# keyboard.net
KiCad netlist of a schematic drawn in Altium Designer
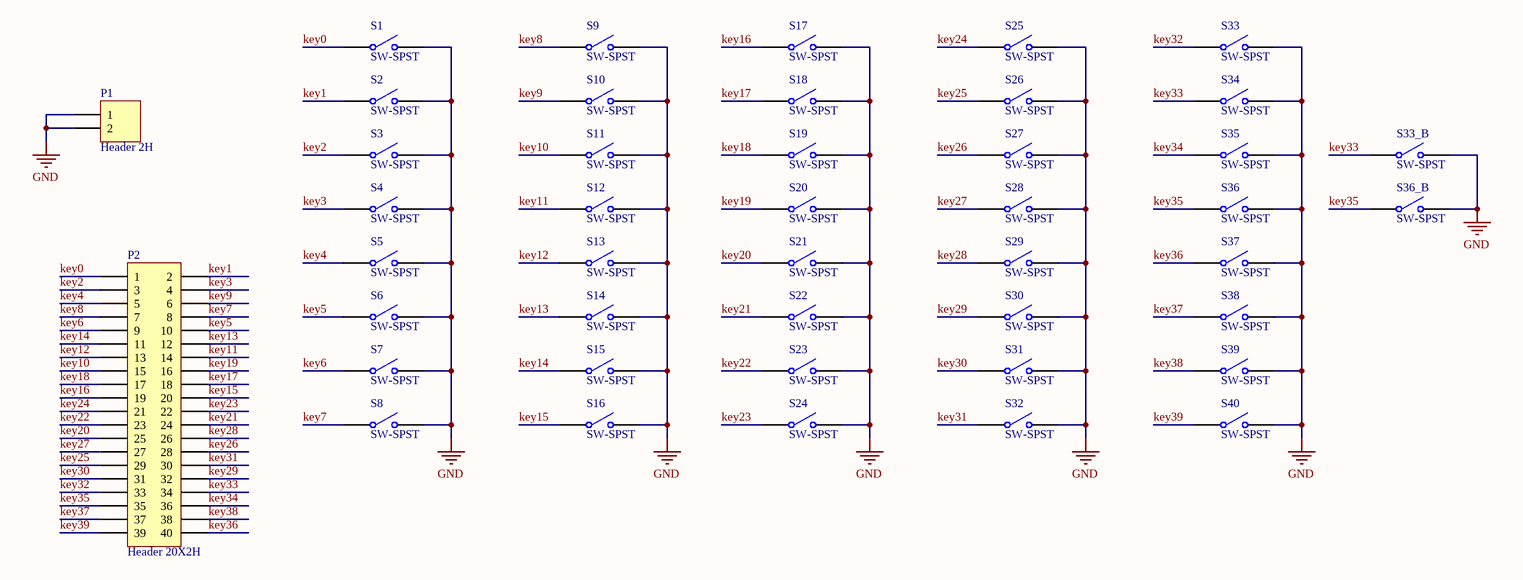
[diagram p0: keyboard.SchDoc]

(export (version "E")
  (design (tool "Eeschema 10.0.6"))
  (components
    (comp (ref "P1")
      (value "Header 2H")
      (footprint "HDR1X2H")
      (description "Header, 2-Pin, Right Angle")
      (fields (field (name "PUBLISHER") "Altium Limited"))
      (libsource (lib "Miscellaneous Connectors") (part "Header 2H"))
    )
    (comp (ref "P2")
      (value "Header 20X2H")
      (footprint "HDR2X20H")
      (description "Header, 20-Pin, Dual row, Right Angle")
      (fields (field (name "PUBLISHER") "Altium Limited"))
      (libsource (lib "Miscellaneous Connectors") (part "Header 20X2H"))
    )
    (comp (ref "S1")
      (value "SW-SPST")
      (footprint "CherryMxSwitchNoLED")
      (description "Single-Pole, Single-Throw Switch")
      (fields (field (name "PUBLISHER") "Altium Limited"))
      (libsource (lib "Miscellaneous Devices") (part "SW-SPST"))
    )
    (comp (ref "S2")
      (value "SW-SPST")
      (footprint "CherryMxSwitchNoLED")
      (description "Single-Pole, Single-Throw Switch")
      (fields (field (name "PUBLISHER") "Altium Limited"))
      (libsource (lib "Miscellaneous Devices") (part "SW-SPST"))
    )
    (comp (ref "S3")
      (value "SW-SPST")
      (footprint "CherryMxSwitchNoLED")
      (description "Single-Pole, Single-Throw Switch")
      (fields (field (name "PUBLISHER") "Altium Limited"))
      (libsource (lib "Miscellaneous Devices") (part "SW-SPST"))
    )
    (comp (ref "S4")
      (value "SW-SPST")
      (footprint "CherryMxSwitchNoLED")
      (description "Single-Pole, Single-Throw Switch")
      (fields (field (name "PUBLISHER") "Altium Limited"))
      (libsource (lib "Miscellaneous Devices") (part "SW-SPST"))
    )
    (comp (ref "S5")
      (value "SW-SPST")
      (footprint "CherryMxSwitchNoLED")
      (description "Single-Pole, Single-Throw Switch")
      (fields (field (name "PUBLISHER") "Altium Limited"))
      (libsource (lib "Miscellaneous Devices") (part "SW-SPST"))
    )
    (comp (ref "S6")
      (value "SW-SPST")
      (footprint "CherryMxSwitchNoLED")
      (description "Single-Pole, Single-Throw Switch")
      (fields (field (name "PUBLISHER") "Altium Limited"))
      (libsource (lib "Miscellaneous Devices") (part "SW-SPST"))
    )
    (comp (ref "S7")
      (value "SW-SPST")
      (footprint "CherryMxSwitchNoLED")
      (description "Single-Pole, Single-Throw Switch")
      (fields (field (name "PUBLISHER") "Altium Limited"))
      (libsource (lib "Miscellaneous Devices") (part "SW-SPST"))
    )
    (comp (ref "S8")
      (value "SW-SPST")
      (footprint "CherryMxSwitchNoLED")
      (description "Single-Pole, Single-Throw Switch")
      (fields (field (name "PUBLISHER") "Altium Limited"))
      (libsource (lib "Miscellaneous Devices") (part "SW-SPST"))
    )
    (comp (ref "S9")
      (value "SW-SPST")
      (footprint "CherryMxSwitchNoLED")
      (description "Single-Pole, Single-Throw Switch")
      (fields (field (name "PUBLISHER") "Altium Limited"))
      (libsource (lib "Miscellaneous Devices") (part "SW-SPST"))
    )
    (comp (ref "S10")
      (value "SW-SPST")
      (footprint "CherryMxSwitchNoLED")
      (description "Single-Pole, Single-Throw Switch")
      (fields (field (name "PUBLISHER") "Altium Limited"))
      (libsource (lib "Miscellaneous Devices") (part "SW-SPST"))
    )
    (comp (ref "S11")
      (value "SW-SPST")
      (footprint "CherryMxSwitchNoLED")
      (description "Single-Pole, Single-Throw Switch")
      (fields (field (name "PUBLISHER") "Altium Limited"))
      (libsource (lib "Miscellaneous Devices") (part "SW-SPST"))
    )
    (comp (ref "S12")
      (value "SW-SPST")
      (footprint "CherryMxSwitchNoLED")
      (description "Single-Pole, Single-Throw Switch")
      (fields (field (name "PUBLISHER") "Altium Limited"))
      (libsource (lib "Miscellaneous Devices") (part "SW-SPST"))
    )
    (comp (ref "S13")
      (value "SW-SPST")
      (footprint "CherryMxSwitchNoLED")
      (description "Single-Pole, Single-Throw Switch")
      (fields (field (name "PUBLISHER") "Altium Limited"))
      (libsource (lib "Miscellaneous Devices") (part "SW-SPST"))
    )
    (comp (ref "S14")
      (value "SW-SPST")
      (footprint "CherryMxSwitchNoLED")
      (description "Single-Pole, Single-Throw Switch")
      (fields (field (name "PUBLISHER") "Altium Limited"))
      (libsource (lib "Miscellaneous Devices") (part "SW-SPST"))
    )
    (comp (ref "S15")
      (value "SW-SPST")
      (footprint "CherryMxSwitchNoLED")
      (description "Single-Pole, Single-Throw Switch")
      (fields (field (name "PUBLISHER") "Altium Limited"))
      (libsource (lib "Miscellaneous Devices") (part "SW-SPST"))
    )
    (comp (ref "S16")
      (value "SW-SPST")
      (footprint "CherryMxSwitchNoLED")
      (description "Single-Pole, Single-Throw Switch")
      (fields (field (name "PUBLISHER") "Altium Limited"))
      (libsource (lib "Miscellaneous Devices") (part "SW-SPST"))
    )
    (comp (ref "S17")
      (value "SW-SPST")
      (footprint "CherryMxSwitchNoLED")
      (description "Single-Pole, Single-Throw Switch")
      (fields (field (name "PUBLISHER") "Altium Limited"))
      (libsource (lib "Miscellaneous Devices") (part "SW-SPST"))
    )
    (comp (ref "S18")
      (value "SW-SPST")
      (footprint "CherryMxSwitchNoLED")
      (description "Single-Pole, Single-Throw Switch")
      (fields (field (name "PUBLISHER") "Altium Limited"))
      (libsource (lib "Miscellaneous Devices") (part "SW-SPST"))
    )
    (comp (ref "S19")
      (value "SW-SPST")
      (footprint "CherryMxSwitchNoLED")
      (description "Single-Pole, Single-Throw Switch")
      (fields (field (name "PUBLISHER") "Altium Limited"))
      (libsource (lib "Miscellaneous Devices") (part "SW-SPST"))
    )
    (comp (ref "S20")
      (value "SW-SPST")
      (footprint "CherryMxSwitchNoLED")
      (description "Single-Pole, Single-Throw Switch")
      (fields (field (name "PUBLISHER") "Altium Limited"))
      (libsource (lib "Miscellaneous Devices") (part "SW-SPST"))
    )
    (comp (ref "S21")
      (value "SW-SPST")
      (footprint "CherryMxSwitchNoLED")
      (description "Single-Pole, Single-Throw Switch")
      (fields (field (name "PUBLISHER") "Altium Limited"))
      (libsource (lib "Miscellaneous Devices") (part "SW-SPST"))
    )
    (comp (ref "S22")
      (value "SW-SPST")
      (footprint "CherryMxSwitchNoLED")
      (description "Single-Pole, Single-Throw Switch")
      (fields (field (name "PUBLISHER") "Altium Limited"))
      (libsource (lib "Miscellaneous Devices") (part "SW-SPST"))
    )
    (comp (ref "S23")
      (value "SW-SPST")
      (footprint "CherryMxSwitchNoLED")
      (description "Single-Pole, Single-Throw Switch")
      (fields (field (name "PUBLISHER") "Altium Limited"))
      (libsource (lib "Miscellaneous Devices") (part "SW-SPST"))
    )
    (comp (ref "S24")
      (value "SW-SPST")
      (footprint "CherryMxSwitchNoLED")
      (description "Single-Pole, Single-Throw Switch")
      (fields (field (name "PUBLISHER") "Altium Limited"))
      (libsource (lib "Miscellaneous Devices") (part "SW-SPST"))
    )
    (comp (ref "S25")
      (value "SW-SPST")
      (footprint "CherryMxSwitchNoLED")
      (description "Single-Pole, Single-Throw Switch")
      (fields (field (name "PUBLISHER") "Altium Limited"))
      (libsource (lib "Miscellaneous Devices") (part "SW-SPST"))
    )
    (comp (ref "S26")
      (value "SW-SPST")
      (footprint "CherryMxSwitchNoLED")
      (description "Single-Pole, Single-Throw Switch")
      (fields (field (name "PUBLISHER") "Altium Limited"))
      (libsource (lib "Miscellaneous Devices") (part "SW-SPST"))
    )
    (comp (ref "S27")
      (value "SW-SPST")
      (footprint "CherryMxSwitchNoLED")
      (description "Single-Pole, Single-Throw Switch")
      (fields (field (name "PUBLISHER") "Altium Limited"))
      (libsource (lib "Miscellaneous Devices") (part "SW-SPST"))
    )
    (comp (ref "S28")
      (value "SW-SPST")
      (footprint "CherryMxSwitchNoLED")
      (description "Single-Pole, Single-Throw Switch")
      (fields (field (name "PUBLISHER") "Altium Limited"))
      (libsource (lib "Miscellaneous Devices") (part "SW-SPST"))
    )
    (comp (ref "S29")
      (value "SW-SPST")
      (footprint "CherryMxSwitchNoLED")
      (description "Single-Pole, Single-Throw Switch")
      (fields (field (name "PUBLISHER") "Altium Limited"))
      (libsource (lib "Miscellaneous Devices") (part "SW-SPST"))
    )
    (comp (ref "S30")
      (value "SW-SPST")
      (footprint "CherryMxSwitchNoLED")
      (description "Single-Pole, Single-Throw Switch")
      (fields (field (name "PUBLISHER") "Altium Limited"))
      (libsource (lib "Miscellaneous Devices") (part "SW-SPST"))
    )
    (comp (ref "S31")
      (value "SW-SPST")
      (footprint "CherryMxSwitchNoLED")
      (description "Single-Pole, Single-Throw Switch")
      (fields (field (name "PUBLISHER") "Altium Limited"))
      (libsource (lib "Miscellaneous Devices") (part "SW-SPST"))
    )
    (comp (ref "S32")
      (value "SW-SPST")
      (footprint "CherryMxSwitchNoLED")
      (description "Single-Pole, Single-Throw Switch")
      (fields (field (name "PUBLISHER") "Altium Limited"))
      (libsource (lib "Miscellaneous Devices") (part "SW-SPST"))
    )
    (comp (ref "S33")
      (value "SW-SPST")
      (footprint "CherryMxSwitchNoLED")
      (description "Single-Pole, Single-Throw Switch")
      (fields (field (name "PUBLISHER") "Altium Limited"))
      (libsource (lib "Miscellaneous Devices") (part "SW-SPST"))
    )
    (comp (ref "S33_B")
      (value "SW-SPST")
      (footprint "CherryMxSwitchNoLED")
      (description "Single-Pole, Single-Throw Switch")
      (fields (field (name "PUBLISHER") "Altium Limited"))
      (libsource (lib "Miscellaneous Devices") (part "SW-SPST"))
    )
    (comp (ref "S34")
      (value "SW-SPST")
      (footprint "CherryMxSwitchNoLED")
      (description "Single-Pole, Single-Throw Switch")
      (fields (field (name "PUBLISHER") "Altium Limited"))
      (libsource (lib "Miscellaneous Devices") (part "SW-SPST"))
    )
    (comp (ref "S35")
      (value "SW-SPST")
      (footprint "CherryMxSwitchNoLED")
      (description "Single-Pole, Single-Throw Switch")
      (fields (field (name "PUBLISHER") "Altium Limited"))
      (libsource (lib "Miscellaneous Devices") (part "SW-SPST"))
    )
    (comp (ref "S36")
      (value "SW-SPST")
      (footprint "CherryMxSwitchNoLED")
      (description "Single-Pole, Single-Throw Switch")
      (fields (field (name "PUBLISHER") "Altium Limited"))
      (libsource (lib "Miscellaneous Devices") (part "SW-SPST"))
    )
    (comp (ref "S36_B")
      (value "SW-SPST")
      (footprint "CherryMxSwitchNoLED")
      (description "Single-Pole, Single-Throw Switch")
      (fields (field (name "PUBLISHER") "Altium Limited"))
      (libsource (lib "Miscellaneous Devices") (part "SW-SPST"))
    )
    (comp (ref "S37")
      (value "SW-SPST")
      (footprint "CherryMxSwitchNoLED")
      (description "Single-Pole, Single-Throw Switch")
      (fields (field (name "PUBLISHER") "Altium Limited"))
      (libsource (lib "Miscellaneous Devices") (part "SW-SPST"))
    )
    (comp (ref "S38")
      (value "SW-SPST")
      (footprint "CherryMxSwitchNoLED")
      (description "Single-Pole, Single-Throw Switch")
      (fields (field (name "PUBLISHER") "Altium Limited"))
      (libsource (lib "Miscellaneous Devices") (part "SW-SPST"))
    )
    (comp (ref "S39")
      (value "SW-SPST")
      (footprint "CherryMxSwitchNoLED")
      (description "Single-Pole, Single-Throw Switch")
      (fields (field (name "PUBLISHER") "Altium Limited"))
      (libsource (lib "Miscellaneous Devices") (part "SW-SPST"))
    )
    (comp (ref "S40")
      (value "SW-SPST")
      (footprint "CherryMxSwitchNoLED")
      (description "Single-Pole, Single-Throw Switch")
      (fields (field (name "PUBLISHER") "Altium Limited"))
      (libsource (lib "Miscellaneous Devices") (part "SW-SPST"))
    )
  )
  (nets
    (net (code "1") (name "/key0") (class "Default")
      (node (ref "P2") (pin "1") (pinfunction "1_1") (pintype "passive"))
      (node (ref "S1") (pin "1") (pinfunction "COMMON_1") (pintype "passive"))
    )
    (net (code "2") (name "/key1") (class "Default")
      (node (ref "P2") (pin "2") (pinfunction "2_2") (pintype "passive"))
      (node (ref "S2") (pin "1") (pinfunction "COMMON_1") (pintype "passive"))
    )
    (net (code "3") (name "/key2") (class "Default")
      (node (ref "P2") (pin "3") (pinfunction "3_3") (pintype "passive"))
      (node (ref "S3") (pin "1") (pinfunction "COMMON_1") (pintype "passive"))
    )
    (net (code "4") (name "/key3") (class "Default")
      (node (ref "P2") (pin "4") (pinfunction "4_4") (pintype "passive"))
      (node (ref "S4") (pin "1") (pinfunction "COMMON_1") (pintype "passive"))
    )
    (net (code "5") (name "/key4") (class "Default")
      (node (ref "P2") (pin "5") (pinfunction "5_5") (pintype "passive"))
      (node (ref "S5") (pin "1") (pinfunction "COMMON_1") (pintype "passive"))
    )
    (net (code "6") (name "/key5") (class "Default")
      (node (ref "P2") (pin "10") (pinfunction "10_10") (pintype "passive"))
      (node (ref "S6") (pin "1") (pinfunction "COMMON_1") (pintype "passive"))
    )
    (net (code "7") (name "/key6") (class "Default")
      (node (ref "P2") (pin "9") (pinfunction "9_9") (pintype "passive"))
      (node (ref "S7") (pin "1") (pinfunction "COMMON_1") (pintype "passive"))
    )
    (net (code "8") (name "/key7") (class "Default")
      (node (ref "P2") (pin "8") (pinfunction "8_8") (pintype "passive"))
      (node (ref "S8") (pin "1") (pinfunction "COMMON_1") (pintype "passive"))
    )
    (net (code "9") (name "/key8") (class "Default")
      (node (ref "P2") (pin "7") (pinfunction "7_7") (pintype "passive"))
      (node (ref "S9") (pin "1") (pinfunction "COMMON_1") (pintype "passive"))
    )
    (net (code "10") (name "/key9") (class "Default")
      (node (ref "P2") (pin "6") (pinfunction "6_6") (pintype "passive"))
      (node (ref "S10") (pin "1") (pinfunction "COMMON_1") (pintype "passive"))
    )
    (net (code "11") (name "/key10") (class "Default")
      (node (ref "P2") (pin "15") (pinfunction "15_15") (pintype "passive"))
      (node (ref "S11") (pin "1") (pinfunction "COMMON_1") (pintype "passive"))
    )
    (net (code "12") (name "/key11") (class "Default")
      (node (ref "P2") (pin "14") (pinfunction "14_14") (pintype "passive"))
      (node (ref "S12") (pin "1") (pinfunction "COMMON_1") (pintype "passive"))
    )
    (net (code "13") (name "/key12") (class "Default")
      (node (ref "P2") (pin "13") (pinfunction "13_13") (pintype "passive"))
      (node (ref "S13") (pin "1") (pinfunction "COMMON_1") (pintype "passive"))
    )
    (net (code "14") (name "/key13") (class "Default")
      (node (ref "P2") (pin "12") (pinfunction "12_12") (pintype "passive"))
      (node (ref "S14") (pin "1") (pinfunction "COMMON_1") (pintype "passive"))
    )
    (net (code "15") (name "/key14") (class "Default")
      (node (ref "P2") (pin "11") (pinfunction "11_11") (pintype "passive"))
      (node (ref "S15") (pin "1") (pinfunction "COMMON_1") (pintype "passive"))
    )
    (net (code "16") (name "/key15") (class "Default")
      (node (ref "P2") (pin "20") (pinfunction "20_20") (pintype "passive"))
      (node (ref "S16") (pin "1") (pinfunction "COMMON_1") (pintype "passive"))
    )
    (net (code "17") (name "/key16") (class "Default")
      (node (ref "P2") (pin "19") (pinfunction "19_19") (pintype "passive"))
      (node (ref "S17") (pin "1") (pinfunction "COMMON_1") (pintype "passive"))
    )
    (net (code "18") (name "/key17") (class "Default")
      (node (ref "P2") (pin "18") (pinfunction "18_18") (pintype "passive"))
      (node (ref "S18") (pin "1") (pinfunction "COMMON_1") (pintype "passive"))
    )
    (net (code "19") (name "/key18") (class "Default")
      (node (ref "P2") (pin "17") (pinfunction "17_17") (pintype "passive"))
      (node (ref "S19") (pin "1") (pinfunction "COMMON_1") (pintype "passive"))
    )
    (net (code "20") (name "/key19") (class "Default")
      (node (ref "P2") (pin "16") (pinfunction "16_16") (pintype "passive"))
      (node (ref "S20") (pin "1") (pinfunction "COMMON_1") (pintype "passive"))
    )
    (net (code "21") (name "/key20") (class "Default")
      (node (ref "P2") (pin "25") (pinfunction "25_25") (pintype "passive"))
      (node (ref "S21") (pin "1") (pinfunction "COMMON_1") (pintype "passive"))
    )
    (net (code "22") (name "/key21") (class "Default")
      (node (ref "P2") (pin "24") (pinfunction "24_24") (pintype "passive"))
      (node (ref "S22") (pin "1") (pinfunction "COMMON_1") (pintype "passive"))
    )
    (net (code "23") (name "/key22") (class "Default")
      (node (ref "P2") (pin "23") (pinfunction "23_23") (pintype "passive"))
      (node (ref "S23") (pin "1") (pinfunction "COMMON_1") (pintype "passive"))
    )
    (net (code "24") (name "/key23") (class "Default")
      (node (ref "P2") (pin "22") (pinfunction "22_22") (pintype "passive"))
      (node (ref "S24") (pin "1") (pinfunction "COMMON_1") (pintype "passive"))
    )
    (net (code "25") (name "/key24") (class "Default")
      (node (ref "P2") (pin "21") (pinfunction "21_21") (pintype "passive"))
      (node (ref "S25") (pin "1") (pinfunction "COMMON_1") (pintype "passive"))
    )
    (net (code "26") (name "/key25") (class "Default")
      (node (ref "P2") (pin "29") (pinfunction "29_29") (pintype "passive"))
      (node (ref "S26") (pin "1") (pinfunction "COMMON_1") (pintype "passive"))
    )
    (net (code "27") (name "/key26") (class "Default")
      (node (ref "P2") (pin "28") (pinfunction "28_28") (pintype "passive"))
      (node (ref "S27") (pin "1") (pinfunction "COMMON_1") (pintype "passive"))
    )
    (net (code "28") (name "/key27") (class "Default")
      (node (ref "P2") (pin "27") (pinfunction "27_27") (pintype "passive"))
      (node (ref "S28") (pin "1") (pinfunction "COMMON_1") (pintype "passive"))
    )
    (net (code "29") (name "/key28") (class "Default")
      (node (ref "P2") (pin "26") (pinfunction "26_26") (pintype "passive"))
      (node (ref "S29") (pin "1") (pinfunction "COMMON_1") (pintype "passive"))
    )
    (net (code "30") (name "/key29") (class "Default")
      (node (ref "P2") (pin "32") (pinfunction "32_32") (pintype "passive"))
      (node (ref "S30") (pin "1") (pinfunction "COMMON_1") (pintype "passive"))
    )
    (net (code "31") (name "/key30") (class "Default")
      (node (ref "P2") (pin "31") (pinfunction "31_31") (pintype "passive"))
      (node (ref "S31") (pin "1") (pinfunction "COMMON_1") (pintype "passive"))
    )
    (net (code "32") (name "/key31") (class "Default")
      (node (ref "P2") (pin "30") (pinfunction "30_30") (pintype "passive"))
      (node (ref "S32") (pin "1") (pinfunction "COMMON_1") (pintype "passive"))
    )
    (net (code "33") (name "/key32") (class "Default")
      (node (ref "P2") (pin "33") (pinfunction "33_33") (pintype "passive"))
      (node (ref "S33") (pin "1") (pinfunction "COMMON_1") (pintype "passive"))
    )
    (net (code "34") (name "/key33") (class "Default")
      (node (ref "P2") (pin "34") (pinfunction "34_34") (pintype "passive"))
      (node (ref "S33_B") (pin "1") (pinfunction "COMMON_1") (pintype "passive"))
      (node (ref "S34") (pin "1") (pinfunction "COMMON_1") (pintype "passive"))
    )
    (net (code "35") (name "/key34") (class "Default")
      (node (ref "P2") (pin "36") (pinfunction "36_36") (pintype "passive"))
      (node (ref "S35") (pin "1") (pinfunction "COMMON_1") (pintype "passive"))
    )
    (net (code "36") (name "/key35") (class "Default")
      (node (ref "P2") (pin "35") (pinfunction "35_35") (pintype "passive"))
      (node (ref "S36") (pin "1") (pinfunction "COMMON_1") (pintype "passive"))
      (node (ref "S36_B") (pin "1") (pinfunction "COMMON_1") (pintype "passive"))
    )
    (net (code "37") (name "/key36") (class "Default")
      (node (ref "P2") (pin "40") (pinfunction "40_40") (pintype "passive"))
      (node (ref "S37") (pin "1") (pinfunction "COMMON_1") (pintype "passive"))
    )
    (net (code "38") (name "/key37") (class "Default")
      (node (ref "P2") (pin "37") (pinfunction "37_37") (pintype "passive"))
      (node (ref "S38") (pin "1") (pinfunction "COMMON_1") (pintype "passive"))
    )
    (net (code "39") (name "/key38") (class "Default")
      (node (ref "P2") (pin "38") (pinfunction "38_38") (pintype "passive"))
      (node (ref "S39") (pin "1") (pinfunction "COMMON_1") (pintype "passive"))
    )
    (net (code "40") (name "/key39") (class "Default")
      (node (ref "P2") (pin "39") (pinfunction "39_39") (pintype "passive"))
      (node (ref "S40") (pin "1") (pinfunction "COMMON_1") (pintype "passive"))
    )
    (net (code "41") (name "GND") (class "Default")
      (node (ref "P1") (pin "1") (pinfunction "1_1") (pintype "passive"))
      (node (ref "P1") (pin "2") (pinfunction "2_2") (pintype "passive"))
      (node (ref "S1") (pin "2") (pinfunction "NO_2") (pintype "passive"))
      (node (ref "S10") (pin "2") (pinfunction "NO_2") (pintype "passive"))
      (node (ref "S11") (pin "2") (pinfunction "NO_2") (pintype "passive"))
      (node (ref "S12") (pin "2") (pinfunction "NO_2") (pintype "passive"))
      (node (ref "S13") (pin "2") (pinfunction "NO_2") (pintype "passive"))
      (node (ref "S14") (pin "2") (pinfunction "NO_2") (pintype "passive"))
      (node (ref "S15") (pin "2") (pinfunction "NO_2") (pintype "passive"))
      (node (ref "S16") (pin "2") (pinfunction "NO_2") (pintype "passive"))
      (node (ref "S17") (pin "2") (pinfunction "NO_2") (pintype "passive"))
      (node (ref "S18") (pin "2") (pinfunction "NO_2") (pintype "passive"))
      (node (ref "S19") (pin "2") (pinfunction "NO_2") (pintype "passive"))
      (node (ref "S2") (pin "2") (pinfunction "NO_2") (pintype "passive"))
      (node (ref "S20") (pin "2") (pinfunction "NO_2") (pintype "passive"))
      (node (ref "S21") (pin "2") (pinfunction "NO_2") (pintype "passive"))
      (node (ref "S22") (pin "2") (pinfunction "NO_2") (pintype "passive"))
      (node (ref "S23") (pin "2") (pinfunction "NO_2") (pintype "passive"))
      (node (ref "S24") (pin "2") (pinfunction "NO_2") (pintype "passive"))
      (node (ref "S25") (pin "2") (pinfunction "NO_2") (pintype "passive"))
      (node (ref "S26") (pin "2") (pinfunction "NO_2") (pintype "passive"))
      (node (ref "S27") (pin "2") (pinfunction "NO_2") (pintype "passive"))
      (node (ref "S28") (pin "2") (pinfunction "NO_2") (pintype "passive"))
      (node (ref "S29") (pin "2") (pinfunction "NO_2") (pintype "passive"))
      (node (ref "S3") (pin "2") (pinfunction "NO_2") (pintype "passive"))
      (node (ref "S30") (pin "2") (pinfunction "NO_2") (pintype "passive"))
      (node (ref "S31") (pin "2") (pinfunction "NO_2") (pintype "passive"))
      (node (ref "S32") (pin "2") (pinfunction "NO_2") (pintype "passive"))
      (node (ref "S33") (pin "2") (pinfunction "NO_2") (pintype "passive"))
      (node (ref "S33_B") (pin "2") (pinfunction "NO_2") (pintype "passive"))
      (node (ref "S34") (pin "2") (pinfunction "NO_2") (pintype "passive"))
      (node (ref "S35") (pin "2") (pinfunction "NO_2") (pintype "passive"))
      (node (ref "S36") (pin "2") (pinfunction "NO_2") (pintype "passive"))
      (node (ref "S36_B") (pin "2") (pinfunction "NO_2") (pintype "passive"))
      (node (ref "S37") (pin "2") (pinfunction "NO_2") (pintype "passive"))
      (node (ref "S38") (pin "2") (pinfunction "NO_2") (pintype "passive"))
      (node (ref "S39") (pin "2") (pinfunction "NO_2") (pintype "passive"))
      (node (ref "S4") (pin "2") (pinfunction "NO_2") (pintype "passive"))
      (node (ref "S40") (pin "2") (pinfunction "NO_2") (pintype "passive"))
      (node (ref "S5") (pin "2") (pinfunction "NO_2") (pintype "passive"))
      (node (ref "S6") (pin "2") (pinfunction "NO_2") (pintype "passive"))
      (node (ref "S7") (pin "2") (pinfunction "NO_2") (pintype "passive"))
      (node (ref "S8") (pin "2") (pinfunction "NO_2") (pintype "passive"))
      (node (ref "S9") (pin "2") (pinfunction "NO_2") (pintype "passive"))
    )
  )
)
